# notch_out.net
KiCad netlist of a schematic drawn in Altium Designer
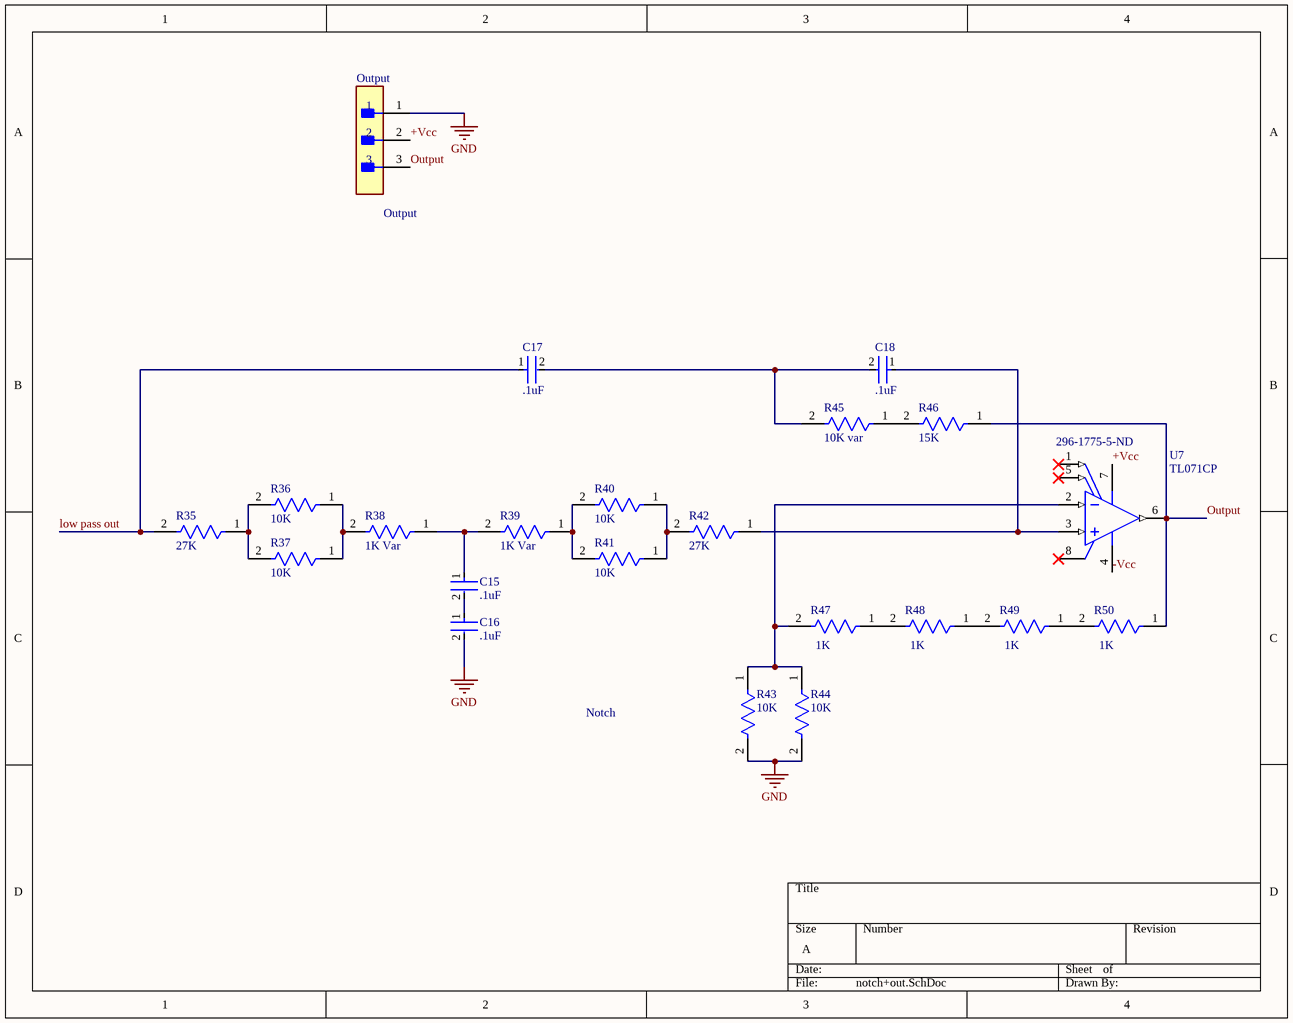
[diagram p0: notch+out.SchDoc]

(export (version "E")
  (design (tool "Eeschema 10.0.6"))
  (components
    (comp (ref "C15")
      (value ".1uF")
      (footprint "FP-K15H5-MFG")
      (description "CAP CER 0.1UF 50V X7R RADIAL")
      (fields (field (name "VOLTAGE") "50V") (field (name "TOLERANCE") "10%"))
      (libsource (lib "Altium Content Vault") (part "11868f565c42a9108669ba33697ecf6"))
    )
    (comp (ref "C16")
      (value ".1uF")
      (footprint "FP-K15H5-MFG")
      (description "CAP CER 0.1UF 50V X7R RADIAL")
      (fields (field (name "VOLTAGE") "50V") (field (name "TOLERANCE") "10%"))
      (libsource (lib "Altium Content Vault") (part "11868f565c42a9108669ba33697ecf6"))
    )
    (comp (ref "C17")
      (value ".1uF")
      (footprint "FP-K15H5-MFG")
      (description "CAP CER 0.1UF 50V X7R RADIAL")
      (fields (field (name "VOLTAGE") "50V") (field (name "TOLERANCE") "10%"))
      (libsource (lib "Altium Content Vault") (part "11868f565c42a9108669ba33697ecf6"))
    )
    (comp (ref "C18")
      (value ".1uF")
      (footprint "FP-K15H5-MFG")
      (description "CAP CER 0.1UF 50V X7R RADIAL")
      (fields (field (name "VOLTAGE") "50V") (field (name "TOLERANCE") "10%"))
      (libsource (lib "Altium Content Vault") (part "11868f565c42a9108669ba33697ecf6"))
    )
    (comp (ref "Output")
      (value "87224-3")
      (footprint "FP-87224-3-MFG")
      (description "CONN HEADER VERT 3POS 2.54MM")
      (libsource (lib "Altium Content Vault") (part "0d3f023dd272f625e17a2be33dea85f"))
    )
    (comp (ref "R35")
      (value "27K")
      (footprint "FP-CFR-25-MFG")
      (description "RES 10 OHM 1/4W 5% AXIAL")
      (fields (field (name "TOLERANCE") "5%"))
      (libsource (lib "Altium Content Vault") (part "1029c3af85768c4190bb7ad29bc67b5"))
    )
    (comp (ref "R36")
      (value "10K")
      (footprint "FP-CFR-25-MFG")
      (description "RES 10 OHM 1/4W 5% AXIAL")
      (fields (field (name "TOLERANCE") "5%"))
      (libsource (lib "Altium Content Vault") (part "1029c3af85768c4190bb7ad29bc67b5"))
    )
    (comp (ref "R37")
      (value "10K")
      (footprint "FP-CFR-25-MFG")
      (description "RES 10 OHM 1/4W 5% AXIAL")
      (fields (field (name "TOLERANCE") "5%"))
      (libsource (lib "Altium Content Vault") (part "1029c3af85768c4190bb7ad29bc67b5"))
    )
    (comp (ref "R38")
      (value "1K Var")
      (footprint "FP-CFR-25-MFG")
      (description "RES 10 OHM 1/4W 5% AXIAL")
      (fields (field (name "TOLERANCE") "5%"))
      (libsource (lib "Altium Content Vault") (part "1029c3af85768c4190bb7ad29bc67b5"))
    )
    (comp (ref "R39")
      (value "1K Var")
      (footprint "FP-CFR-25-MFG")
      (description "RES 10 OHM 1/4W 5% AXIAL")
      (fields (field (name "TOLERANCE") "5%"))
      (libsource (lib "Altium Content Vault") (part "1029c3af85768c4190bb7ad29bc67b5"))
    )
    (comp (ref "R40")
      (value "10K")
      (footprint "FP-CFR-25-MFG")
      (description "RES 10 OHM 1/4W 5% AXIAL")
      (fields (field (name "TOLERANCE") "5%"))
      (libsource (lib "Altium Content Vault") (part "1029c3af85768c4190bb7ad29bc67b5"))
    )
    (comp (ref "R41")
      (value "10K")
      (footprint "FP-CFR-25-MFG")
      (description "RES 10 OHM 1/4W 5% AXIAL")
      (fields (field (name "TOLERANCE") "5%"))
      (libsource (lib "Altium Content Vault") (part "1029c3af85768c4190bb7ad29bc67b5"))
    )
    (comp (ref "R42")
      (value "27K")
      (footprint "FP-CFR-25-MFG")
      (description "RES 10 OHM 1/4W 5% AXIAL")
      (fields (field (name "TOLERANCE") "5%"))
      (libsource (lib "Altium Content Vault") (part "1029c3af85768c4190bb7ad29bc67b5"))
    )
    (comp (ref "R43")
      (value "10K")
      (footprint "FP-CFR-25-MFG")
      (description "RES 10 OHM 1/4W 5% AXIAL")
      (fields (field (name "TOLERANCE") "5%"))
      (libsource (lib "Altium Content Vault") (part "1029c3af85768c4190bb7ad29bc67b5"))
    )
    (comp (ref "R44")
      (value "10K")
      (footprint "FP-CFR-25-MFG")
      (description "RES 10 OHM 1/4W 5% AXIAL")
      (fields (field (name "TOLERANCE") "5%"))
      (libsource (lib "Altium Content Vault") (part "1029c3af85768c4190bb7ad29bc67b5"))
    )
    (comp (ref "R45")
      (value "10K var")
      (footprint "FP-CFR-25-MFG")
      (description "RES 10 OHM 1/4W 5% AXIAL")
      (fields (field (name "TOLERANCE") "5%"))
      (libsource (lib "Altium Content Vault") (part "1029c3af85768c4190bb7ad29bc67b5"))
    )
    (comp (ref "R46")
      (value "15K")
      (footprint "FP-CFR-25-MFG")
      (description "RES 10 OHM 1/4W 5% AXIAL")
      (fields (field (name "TOLERANCE") "5%"))
      (libsource (lib "Altium Content Vault") (part "1029c3af85768c4190bb7ad29bc67b5"))
    )
    (comp (ref "R47")
      (value "1K")
      (footprint "FP-CFR-25-MFG")
      (description "RES 10 OHM 1/4W 5% AXIAL")
      (fields (field (name "TOLERANCE") "5%"))
      (libsource (lib "Altium Content Vault") (part "1029c3af85768c4190bb7ad29bc67b5"))
    )
    (comp (ref "R48")
      (value "1K")
      (footprint "FP-CFR-25-MFG")
      (description "RES 10 OHM 1/4W 5% AXIAL")
      (fields (field (name "TOLERANCE") "5%"))
      (libsource (lib "Altium Content Vault") (part "1029c3af85768c4190bb7ad29bc67b5"))
    )
    (comp (ref "R49")
      (value "1K")
      (footprint "FP-CFR-25-MFG")
      (description "RES 10 OHM 1/4W 5% AXIAL")
      (fields (field (name "TOLERANCE") "5%"))
      (libsource (lib "Altium Content Vault") (part "1029c3af85768c4190bb7ad29bc67b5"))
    )
    (comp (ref "R50")
      (value "1K")
      (footprint "FP-CFR-25-MFG")
      (description "RES 10 OHM 1/4W 5% AXIAL")
      (fields (field (name "TOLERANCE") "5%"))
      (libsource (lib "Altium Content Vault") (part "1029c3af85768c4190bb7ad29bc67b5"))
    )
    (comp (ref "U7")
      (value "TL071CP")
      (footprint "P0008A")
      (fields
        (field (name "MANUFACTURER") "Texas Instruments")
        (field (name "SUPPLIER PART NUMBER 1") "296-1775-5-ND")
      )
      (libsource (lib "Altium Content Vault") (part "TI-AMP-S5-2-8"))
    )
  )
  (nets
    (net (code "1") (name "/+Vcc") (class "Default")
      (node (ref "Output") (pin "2") (pinfunction "2_2") (pintype "passive"))
      (node (ref "U7") (pin "7") (pinfunction "VCC+_7") (pintype "power_in"))
    )
    (net (code "2") (name "/-Vcc") (class "Default")
      (node (ref "U7") (pin "4") (pinfunction "VCC-_4") (pintype "power_in"))
    )
    (net (code "3") (name "/Output") (class "Default")
      (node (ref "Output") (pin "3") (pinfunction "3_3") (pintype "passive"))
      (node (ref "R46") (pin "1") (pinfunction "1_1") (pintype "passive"))
      (node (ref "R50") (pin "1") (pinfunction "1_1") (pintype "passive"))
      (node (ref "U7") (pin "6") (pinfunction "OUT_6") (pintype "output"))
    )
    (net (code "4") (name "/low pass out") (class "Default")
      (node (ref "C17") (pin "1") (pinfunction "1_1") (pintype "passive"))
      (node (ref "R35") (pin "2") (pinfunction "2_2") (pintype "passive"))
    )
    (net (code "5") (name "GND") (class "Default")
      (node (ref "C16") (pin "2") (pinfunction "2_2") (pintype "passive"))
      (node (ref "Output") (pin "1") (pinfunction "1_1") (pintype "passive"))
      (node (ref "R43") (pin "2") (pinfunction "2_2") (pintype "passive"))
      (node (ref "R44") (pin "2") (pinfunction "2_2") (pintype "passive"))
    )
    (net (code "6") (name "Net-(C15-Pad1)") (class "Default")
      (node (ref "C15") (pin "1") (pinfunction "1_1") (pintype "passive"))
      (node (ref "R38") (pin "1") (pinfunction "1_1") (pintype "passive"))
      (node (ref "R39") (pin "2") (pinfunction "2_2") (pintype "passive"))
    )
    (net (code "7") (name "Net-(C15-Pad2)") (class "Default")
      (node (ref "C15") (pin "2") (pinfunction "2_2") (pintype "passive"))
      (node (ref "C16") (pin "1") (pinfunction "1_1") (pintype "passive"))
    )
    (net (code "8") (name "Net-(C17-Pad2)") (class "Default")
      (node (ref "C17") (pin "2") (pinfunction "2_2") (pintype "passive"))
      (node (ref "C18") (pin "2") (pinfunction "2_2") (pintype "passive"))
      (node (ref "R45") (pin "2") (pinfunction "2_2") (pintype "passive"))
    )
    (net (code "9") (name "Net-(R35-Pad1)") (class "Default")
      (node (ref "R35") (pin "1") (pinfunction "1_1") (pintype "passive"))
      (node (ref "R36") (pin "2") (pinfunction "2_2") (pintype "passive"))
      (node (ref "R37") (pin "2") (pinfunction "2_2") (pintype "passive"))
    )
    (net (code "10") (name "Net-(R36-Pad1)") (class "Default")
      (node (ref "R36") (pin "1") (pinfunction "1_1") (pintype "passive"))
      (node (ref "R37") (pin "1") (pinfunction "1_1") (pintype "passive"))
      (node (ref "R38") (pin "2") (pinfunction "2_2") (pintype "passive"))
    )
    (net (code "11") (name "Net-(R39-Pad1)") (class "Default")
      (node (ref "R39") (pin "1") (pinfunction "1_1") (pintype "passive"))
      (node (ref "R40") (pin "2") (pinfunction "2_2") (pintype "passive"))
      (node (ref "R41") (pin "2") (pinfunction "2_2") (pintype "passive"))
    )
    (net (code "12") (name "Net-(R40-Pad1)") (class "Default")
      (node (ref "R40") (pin "1") (pinfunction "1_1") (pintype "passive"))
      (node (ref "R41") (pin "1") (pinfunction "1_1") (pintype "passive"))
      (node (ref "R42") (pin "2") (pinfunction "2_2") (pintype "passive"))
    )
    (net (code "13") (name "Net-(R45-Pad1)") (class "Default")
      (node (ref "R45") (pin "1") (pinfunction "1_1") (pintype "passive"))
      (node (ref "R46") (pin "2") (pinfunction "2_2") (pintype "passive"))
    )
    (net (code "14") (name "Net-(R47-Pad1)") (class "Default")
      (node (ref "R47") (pin "1") (pinfunction "1_1") (pintype "passive"))
      (node (ref "R48") (pin "2") (pinfunction "2_2") (pintype "passive"))
    )
    (net (code "15") (name "Net-(R48-Pad1)") (class "Default")
      (node (ref "R48") (pin "1") (pinfunction "1_1") (pintype "passive"))
      (node (ref "R49") (pin "2") (pinfunction "2_2") (pintype "passive"))
    )
    (net (code "16") (name "Net-(R49-Pad1)") (class "Default")
      (node (ref "R49") (pin "1") (pinfunction "1_1") (pintype "passive"))
      (node (ref "R50") (pin "2") (pinfunction "2_2") (pintype "passive"))
    )
    (net (code "17") (name "Net-(U7-IN+)") (class "Default")
      (node (ref "C18") (pin "1") (pinfunction "1_1") (pintype "passive"))
      (node (ref "R42") (pin "1") (pinfunction "1_1") (pintype "passive"))
      (node (ref "U7") (pin "3") (pinfunction "IN+_3") (pintype "input"))
    )
    (net (code "18") (name "Net-(U7-IN-)") (class "Default")
      (node (ref "R43") (pin "1") (pinfunction "1_1") (pintype "passive"))
      (node (ref "R44") (pin "1") (pinfunction "1_1") (pintype "passive"))
      (node (ref "R47") (pin "2") (pinfunction "2_2") (pintype "passive"))
      (node (ref "U7") (pin "2") (pinfunction "IN-_2") (pintype "input"))
    )
    (net (code "19") (name "unconnected-(U7-NC-Pad8)") (class "Default")
      (node (ref "U7") (pin "8") (pinfunction "NC_8") (pintype "passive+no_connect"))
    )
    (net (code "20") (name "unconnected-(U7-OFFSET_N1-Pad1)") (class "Default")
      (node (ref "U7") (pin "1") (pinfunction "OFFSET_N1_1") (pintype "input+no_connect"))
    )
    (net (code "21") (name "unconnected-(U7-OFFSET_N2-Pad5)") (class "Default")
      (node (ref "U7") (pin "5") (pinfunction "OFFSET_N2_5") (pintype "input+no_connect"))
    )
  )
)
